# dmpcb2.net
KiCad netlist of a schematic drawn in EAGLE
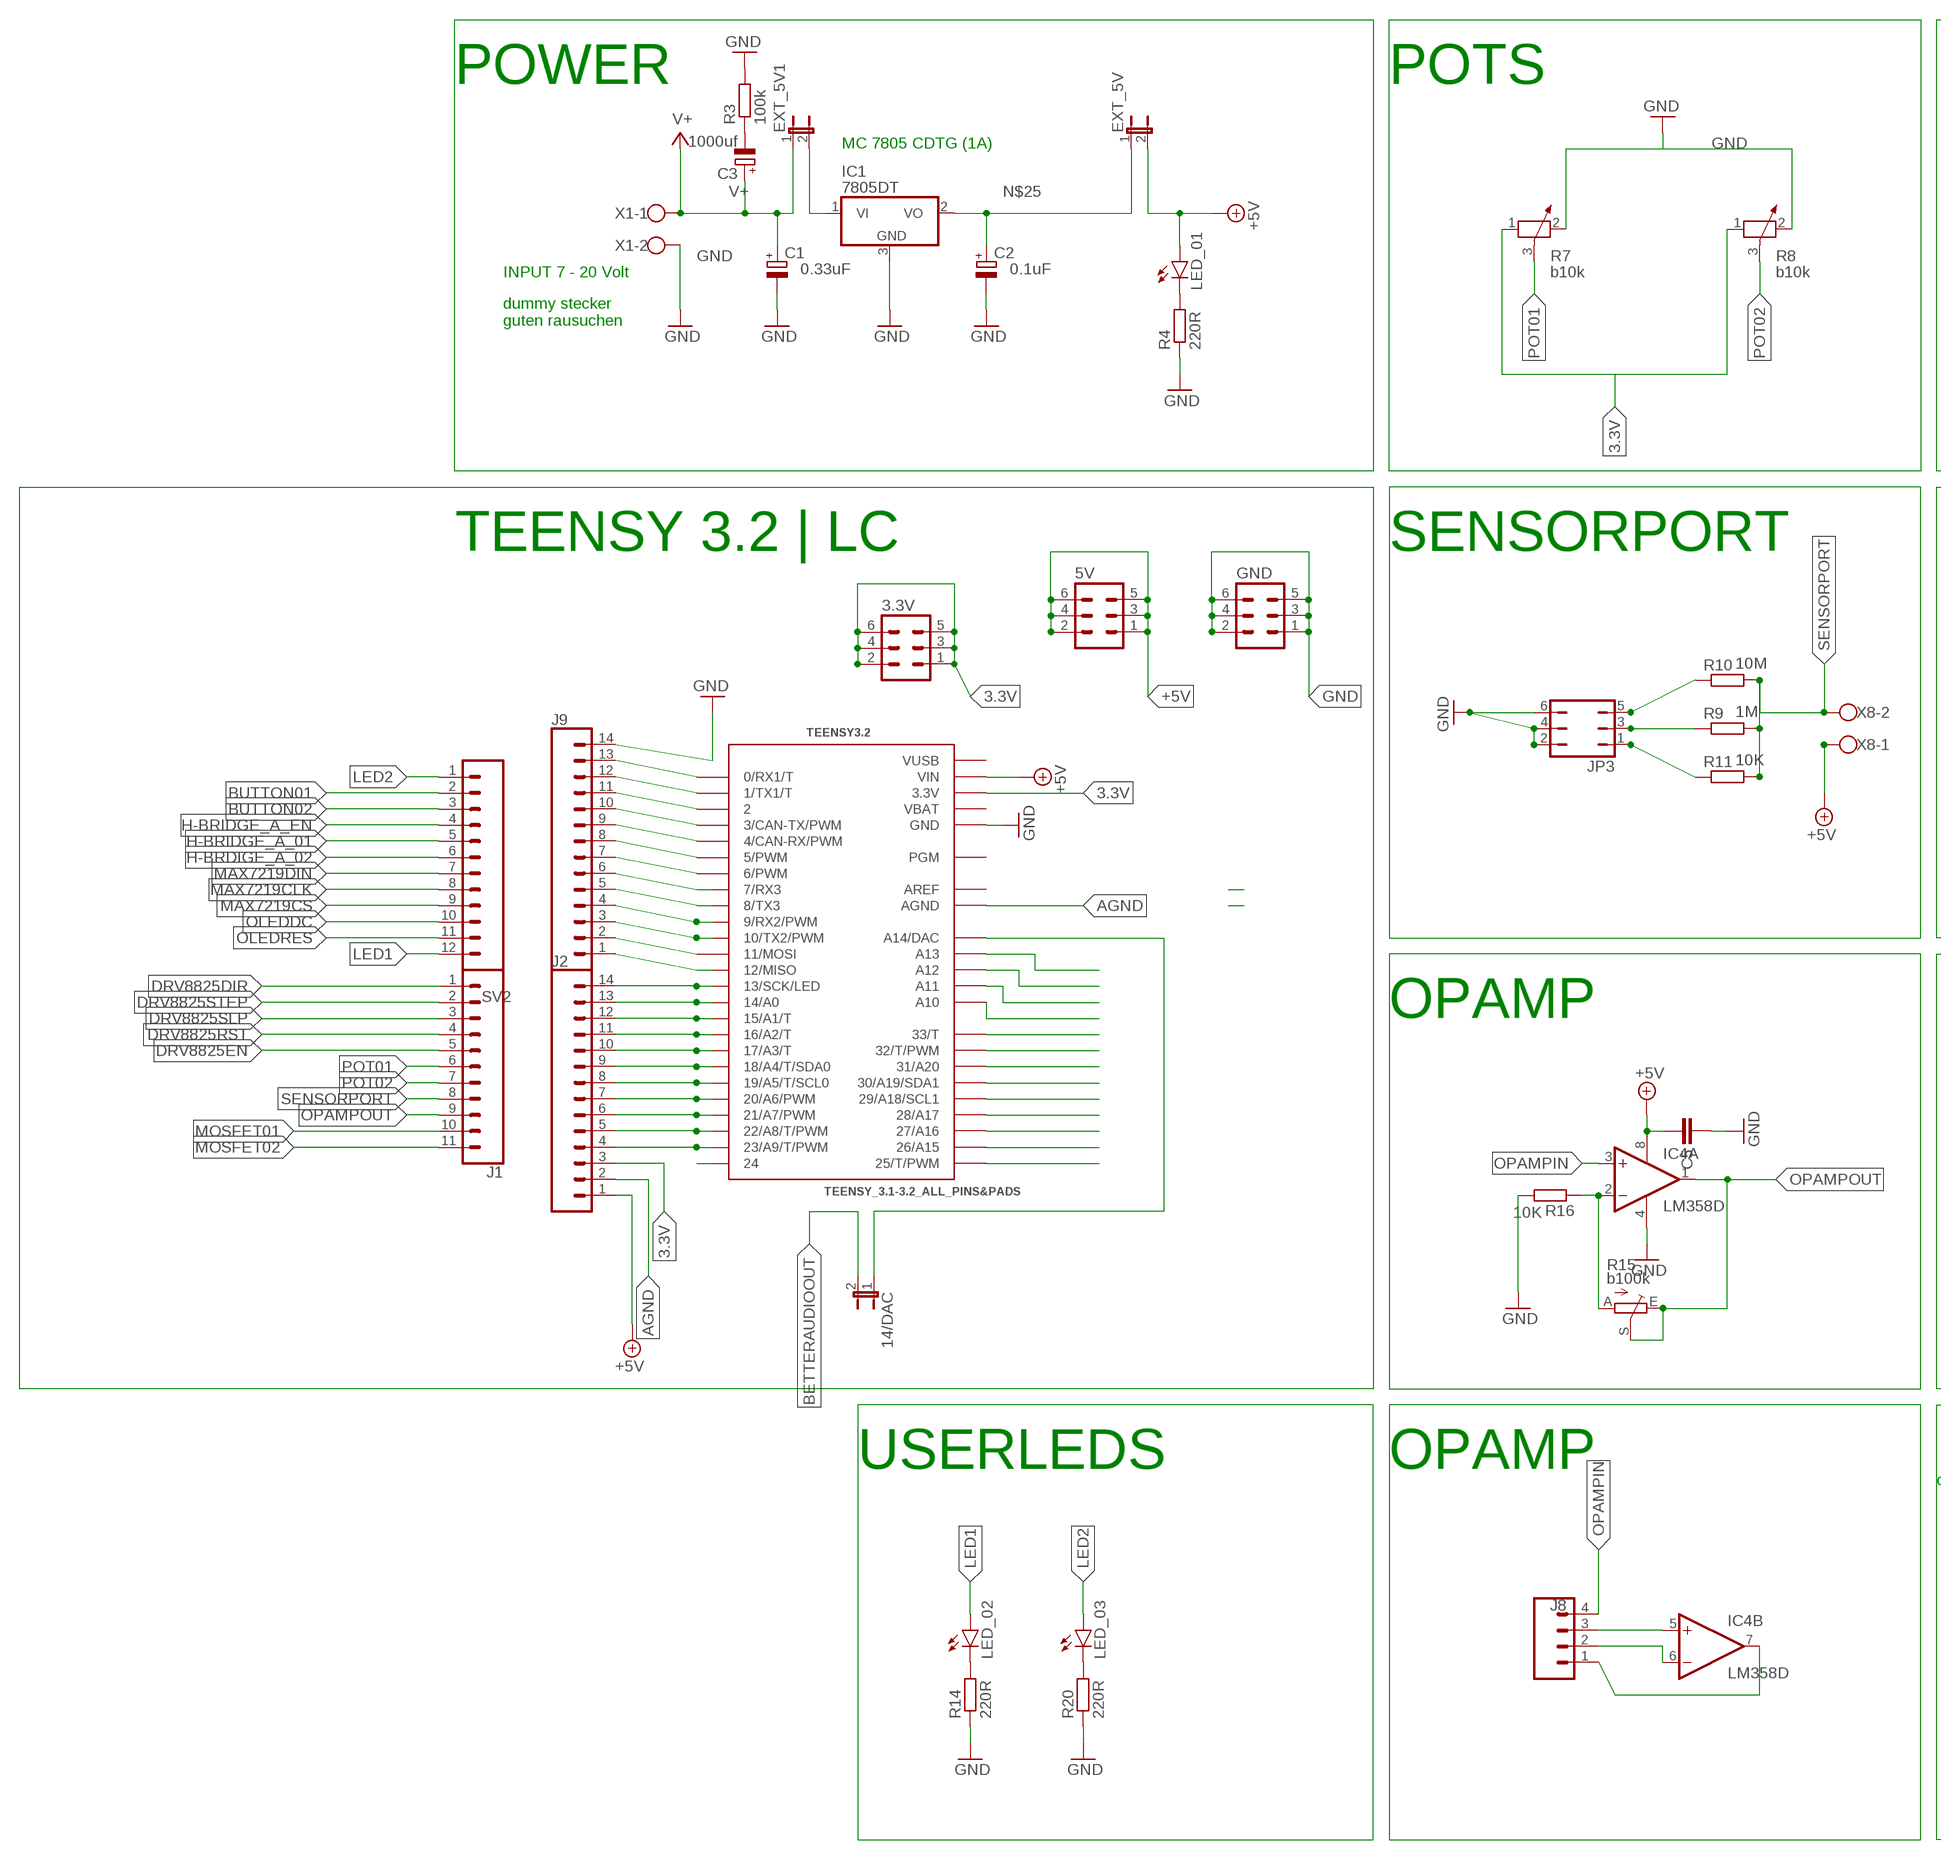
[diagram p0: schematic, sheet 1, part 1 of 2]
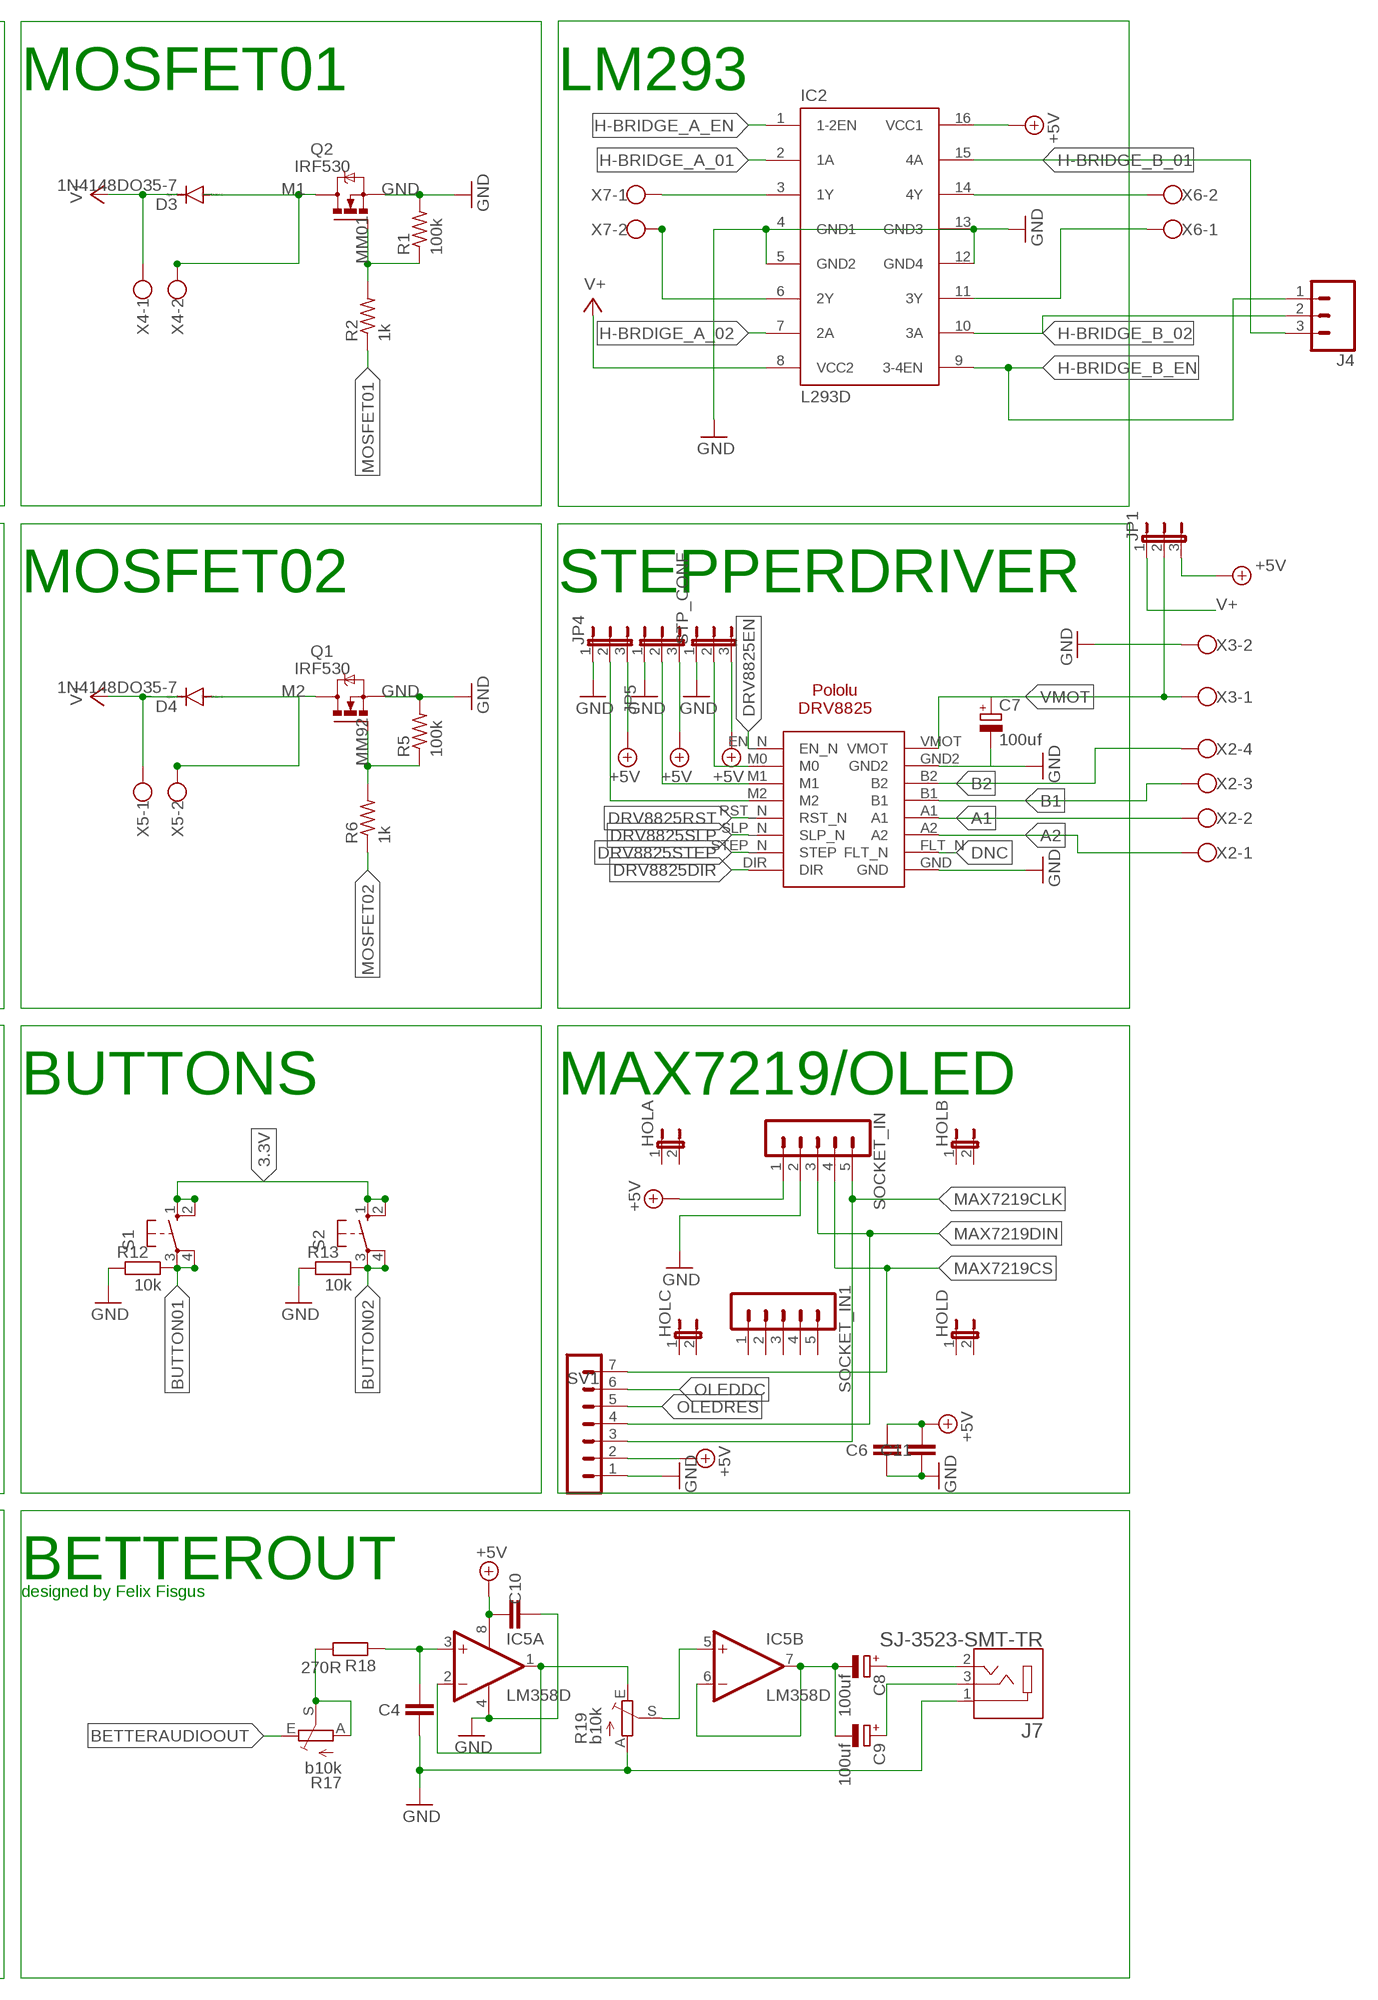
[diagram p1: schematic, sheet 1, part 2 of 2]

(export (version "E")
  (design (tool "Eeschema 10.0.6"))
  (components
    (comp (ref "3.3V")
      (value "MA03-2")
      (footprint "eagle-import:MA03-2")
      (libsource (lib "eagle-import") (part "MA03-2"))
    )
    (comp (ref "5V")
      (value "MA03-2")
      (footprint "eagle-import:MA03-2")
      (libsource (lib "eagle-import") (part "MA03-2"))
    )
    (comp (ref "14/DAC")
      (value "JP1E")
      (footprint "eagle-import:JP1")
      (libsource (lib "eagle-import") (part "JP1E"))
    )
    (comp (ref "C1")
      (value "0.33uF")
      (footprint "eagle-import:SANYO-OSCON_A'")
      (libsource (lib "eagle-import") (part "CPOL-EUSANYO_A'"))
    )
    (comp (ref "C2")
      (value "0.1uF")
      (footprint "eagle-import:SANYO-OSCON_A'")
      (libsource (lib "eagle-import") (part "CPOL-EUSANYO_A'"))
    )
    (comp (ref "C3")
      (value "1000uf")
      (footprint "eagle-import:E3,5-8")
      (libsource (lib "eagle-import") (part "CPOL-EUE3.5-8"))
    )
    (comp (ref "C4")
      (value "100nf")
      (footprint "eagle-import:C0805")
      (libsource (lib "eagle-import") (part "C-EUC0805"))
    )
    (comp (ref "C5")
      (value "100nf")
      (footprint "eagle-import:C0805")
      (libsource (lib "eagle-import") (part "C-EUC0805"))
    )
    (comp (ref "C6")
      (value "100nf")
      (footprint "eagle-import:C0805")
      (libsource (lib "eagle-import") (part "C-EUC0805"))
    )
    (comp (ref "C7")
      (value "100uf")
      (footprint "eagle-import:E5-5")
      (libsource (lib "eagle-import") (part "CPOL-EUE5-5"))
    )
    (comp (ref "C8")
      (value "100uf")
      (footprint "eagle-import:E5-5")
      (libsource (lib "eagle-import") (part "CPOL-EUE5-5"))
    )
    (comp (ref "C9")
      (value "100uf")
      (footprint "eagle-import:E5-5")
      (libsource (lib "eagle-import") (part "CPOL-EUE5-5"))
    )
    (comp (ref "C10")
      (value "100nf")
      (footprint "eagle-import:C0805")
      (libsource (lib "eagle-import") (part "C-EUC0805"))
    )
    (comp (ref "C11")
      (value "10uf")
      (footprint "eagle-import:C0805")
      (libsource (lib "eagle-import") (part "C-EUC0805"))
    )
    (comp (ref "D3")
      (value "1N4148DO35-7")
      (footprint "eagle-import:DO35-7")
      (libsource (lib "eagle-import") (part "1N4148DO35-7"))
    )
    (comp (ref "D4")
      (value "1N4148DO35-7")
      (footprint "eagle-import:DO35-7")
      (libsource (lib "eagle-import") (part "1N4148DO35-7"))
    )
    (comp (ref "DRV8825")
      (value "POLOLU-DRV8825")
      (footprint "eagle-import:POLOLU-DRV8825")
      (libsource (lib "eagle-import") (part "POLOLU-DRV8825"))
    )
    (comp (ref "EXT_5V")
      (value "JP1E")
      (footprint "eagle-import:JP1")
      (libsource (lib "eagle-import") (part "JP1E"))
    )
    (comp (ref "EXT_5V1")
      (value "JP1E")
      (footprint "eagle-import:JP1")
      (libsource (lib "eagle-import") (part "JP1E"))
    )
    (comp (ref "GND")
      (value "MA03-2")
      (footprint "eagle-import:MA03-2")
      (libsource (lib "eagle-import") (part "MA03-2"))
    )
    (comp (ref "HOLA")
      (value "JP1E")
      (footprint "eagle-import:JP1")
      (libsource (lib "eagle-import") (part "JP1E"))
    )
    (comp (ref "HOLB")
      (value "JP1E")
      (footprint "eagle-import:JP1")
      (libsource (lib "eagle-import") (part "JP1E"))
    )
    (comp (ref "HOLC")
      (value "JP1E")
      (footprint "eagle-import:JP1")
      (libsource (lib "eagle-import") (part "JP1E"))
    )
    (comp (ref "HOLD")
      (value "JP1E")
      (footprint "eagle-import:JP1")
      (libsource (lib "eagle-import") (part "JP1E"))
    )
    (comp (ref "IC1")
      (value "7805DT")
      (footprint "eagle-import:TO252")
      (libsource (lib "eagle-import") (part "78DT05"))
    )
    (comp (ref "IC2")
      (value "L293D")
      (footprint "eagle-import:DIL16")
      (libsource (lib "eagle-import") (part "L293D"))
    )
    (comp (ref "IC4")
      (value "LM358D")
      (footprint "eagle-import:SO08")
      (libsource (lib "eagle-import") (part "LM358D"))
    )
    (comp (ref "IC5")
      (value "LM358D")
      (footprint "eagle-import:SO08")
      (libsource (lib "eagle-import") (part "LM358D"))
    )
    (comp (ref "J1")
      (value "CONN_11")
      (footprint "eagle-import:1X11")
      (libsource (lib "eagle-import") (part "CONN_11"))
    )
    (comp (ref "J2")
      (value "CONN_14")
      (footprint "eagle-import:1X14")
      (libsource (lib "eagle-import") (part "CONN_14"))
    )
    (comp (ref "J4")
      (value "CONN_03LOCK_LONGPADS")
      (footprint "eagle-import:1X03_LOCK_LONGPADS")
      (libsource (lib "eagle-import") (part "CONN_03LOCK_LONGPADS"))
    )
    (comp (ref "J7")
      (value "SJ-3523-SMT-TR")
      (footprint "eagle-import:CUI_SJ-3523-SMT-TR")
      (fields (field (name "MF") "CUI Inc"))
      (libsource (lib "eagle-import") (part "SJ-3523-SMT-TR"))
    )
    (comp (ref "J8")
      (value "CONN_04")
      (footprint "eagle-import:1X04")
      (libsource (lib "eagle-import") (part "CONN_04"))
    )
    (comp (ref "J9")
      (value "CONN_14")
      (footprint "eagle-import:1X14")
      (libsource (lib "eagle-import") (part "CONN_14"))
    )
    (comp (ref "JP1")
      (value "JP2E")
      (footprint "eagle-import:JP2")
      (libsource (lib "eagle-import") (part "JP2E"))
    )
    (comp (ref "JP3")
      (value "JP3Q")
      (footprint "eagle-import:JP3Q")
      (libsource (lib "eagle-import") (part "JP3Q"))
    )
    (comp (ref "JP4")
      (value "JP2E")
      (footprint "eagle-import:JP2")
      (libsource (lib "eagle-import") (part "JP2E"))
    )
    (comp (ref "JP5")
      (value "JP2E")
      (footprint "eagle-import:JP2")
      (libsource (lib "eagle-import") (part "JP2E"))
    )
    (comp (ref "LED_01")
      (value "LEDSML0805")
      (footprint "eagle-import:SML0805")
      (libsource (lib "eagle-import") (part "LEDSML0805"))
    )
    (comp (ref "LED_02")
      (value "LEDSML0805")
      (footprint "eagle-import:SML0805")
      (libsource (lib "eagle-import") (part "LEDSML0805"))
    )
    (comp (ref "LED_03")
      (value "LEDSML0805")
      (footprint "eagle-import:SML0805")
      (libsource (lib "eagle-import") (part "LEDSML0805"))
    )
    (comp (ref "Q1")
      (value "IRF530")
      (footprint "eagle-import:TO220BV")
      (libsource (lib "eagle-import") (part "IRF530"))
    )
    (comp (ref "Q2")
      (value "IRF530")
      (footprint "eagle-import:TO220BV")
      (libsource (lib "eagle-import") (part "IRF530"))
    )
    (comp (ref "R1")
      (value "100k")
      (footprint "eagle-import:R0805")
      (libsource (lib "eagle-import") (part "R-US_R0805"))
    )
    (comp (ref "R2")
      (value "1k")
      (footprint "eagle-import:R0805")
      (libsource (lib "eagle-import") (part "R-US_R0805"))
    )
    (comp (ref "R3")
      (value "100k")
      (footprint "eagle-import:R0805")
      (libsource (lib "eagle-import") (part "R-EU_R0805"))
    )
    (comp (ref "R4")
      (value "220R")
      (footprint "eagle-import:R0805")
      (libsource (lib "eagle-import") (part "R-EU_R0805"))
    )
    (comp (ref "R5")
      (value "100k")
      (footprint "eagle-import:R0805")
      (libsource (lib "eagle-import") (part "R-US_R0805"))
    )
    (comp (ref "R6")
      (value "1k")
      (footprint "eagle-import:R0805")
      (libsource (lib "eagle-import") (part "R-US_R0805"))
    )
    (comp (ref "R7")
      (value "b10k")
      (footprint "eagle-import:PT-10")
      (libsource (lib "eagle-import") (part "POTENTIOMETER_PT-10"))
    )
    (comp (ref "R8")
      (value "b10k")
      (footprint "eagle-import:PT-10")
      (libsource (lib "eagle-import") (part "POTENTIOMETER_PT-10"))
    )
    (comp (ref "R9")
      (value "1M")
      (footprint "eagle-import:M0805")
      (libsource (lib "eagle-import") (part "R-EU_M0805"))
    )
    (comp (ref "R10")
      (value "10M")
      (footprint "eagle-import:M0805")
      (libsource (lib "eagle-import") (part "R-EU_M0805"))
    )
    (comp (ref "R11")
      (value "10K")
      (footprint "eagle-import:M0805")
      (libsource (lib "eagle-import") (part "R-EU_M0805"))
    )
    (comp (ref "R12")
      (value "10k")
      (footprint "eagle-import:M0805")
      (libsource (lib "eagle-import") (part "R-EU_M0805"))
    )
    (comp (ref "R13")
      (value "10k")
      (footprint "eagle-import:M0805")
      (libsource (lib "eagle-import") (part "R-EU_M0805"))
    )
    (comp (ref "R14")
      (value "220R")
      (footprint "eagle-import:R0805")
      (libsource (lib "eagle-import") (part "R-EU_R0805"))
    )
    (comp (ref "R15")
      (value "b100k")
      (footprint "eagle-import:RJ9W")
      (libsource (lib "eagle-import") (part "TRIM_EU-RJ9W"))
    )
    (comp (ref "R16")
      (value "10K")
      (footprint "eagle-import:M0805")
      (libsource (lib "eagle-import") (part "R-EU_M0805"))
    )
    (comp (ref "R17")
      (value "b10k")
      (footprint "eagle-import:RJ9W")
      (libsource (lib "eagle-import") (part "TRIM_EU-RJ9W"))
    )
    (comp (ref "R18")
      (value "270R")
      (footprint "eagle-import:M0805")
      (libsource (lib "eagle-import") (part "R-EU_M0805"))
    )
    (comp (ref "R19")
      (value "b10k")
      (footprint "eagle-import:RJ9W")
      (libsource (lib "eagle-import") (part "TRIM_EU-RJ9W"))
    )
    (comp (ref "R20")
      (value "220R")
      (footprint "eagle-import:R0805")
      (libsource (lib "eagle-import") (part "R-EU_R0805"))
    )
    (comp (ref "S1")
      (value "10-XX")
      (footprint "eagle-import:B3F-10XX")
      (fields (field (name "MPN") "B3F-1000"))
      (libsource (lib "eagle-import") (part "10-XX"))
    )
    (comp (ref "S2")
      (value "10-XX")
      (footprint "eagle-import:B3F-10XX")
      (fields (field (name "MPN") "B3F-1000"))
      (libsource (lib "eagle-import") (part "10-XX"))
    )
    (comp (ref "SOCKET_IN")
      (value "MA05-1")
      (footprint "eagle-import:MA05-1")
      (libsource (lib "eagle-import") (part "MA05-1"))
    )
    (comp (ref "SOCKET_IN1")
      (value "MA05-1")
      (footprint "eagle-import:MA05-1")
      (libsource (lib "eagle-import") (part "MA05-1"))
    )
    (comp (ref "STP_CONF")
      (value "JP2E")
      (footprint "eagle-import:JP2")
      (libsource (lib "eagle-import") (part "JP2E"))
    )
    (comp (ref "SV1")
      (value "MA07-1")
      (footprint "eagle-import:MA07-1")
      (libsource (lib "eagle-import") (part "MA07-1"))
    )
    (comp (ref "SV2")
      (value "CONN_12")
      (footprint "eagle-import:1X12")
      (libsource (lib "eagle-import") (part "CONN_12"))
    )
    (comp (ref "TEENSY3.2")
      (value "TEENSY_3.1-3.2_ALL_PINS&PADS")
      (footprint "eagle-import:TEENSY_3.0-3.2_ALL_PINS_&_PADS")
      (libsource (lib "eagle-import") (part "TEENSY_3.1-3.2_ALL_PINS&PADS"))
    )
    (comp (ref "X1")
      (value "W237-102")
      (footprint "eagle-import:W237-102")
      (fields (field (name "MPN") "237-102"))
      (libsource (lib "eagle-import") (part "W237-102"))
    )
    (comp (ref "X2")
      (value "W237-4")
      (footprint "eagle-import:W237-4")
      (libsource (lib "eagle-import") (part "W237-4"))
    )
    (comp (ref "X3")
      (value "W237-102")
      (footprint "eagle-import:W237-102")
      (fields (field (name "MPN") "237-102"))
      (libsource (lib "eagle-import") (part "W237-102"))
    )
    (comp (ref "X4")
      (value "W237-102")
      (footprint "eagle-import:W237-102")
      (fields (field (name "MPN") "237-102"))
      (libsource (lib "eagle-import") (part "W237-102"))
    )
    (comp (ref "X5")
      (value "W237-102")
      (footprint "eagle-import:W237-102")
      (fields (field (name "MPN") "237-102"))
      (libsource (lib "eagle-import") (part "W237-102"))
    )
    (comp (ref "X6")
      (value "W237-102")
      (footprint "eagle-import:W237-102")
      (fields (field (name "MPN") "237-102"))
      (libsource (lib "eagle-import") (part "W237-102"))
    )
    (comp (ref "X7")
      (value "W237-102")
      (footprint "eagle-import:W237-102")
      (fields (field (name "MPN") "237-102"))
      (libsource (lib "eagle-import") (part "W237-102"))
    )
    (comp (ref "X8")
      (value "W237-102")
      (footprint "eagle-import:W237-102")
      (fields (field (name "MPN") "237-102"))
      (libsource (lib "eagle-import") (part "W237-102"))
    )
  )
  (nets
    (net (code "1") (name "+5V") (class "Default")
      (node (ref "5V") (pin "1") (pinfunction "1_1") (pintype "passive"))
      (node (ref "5V") (pin "2") (pinfunction "2_2") (pintype "passive"))
      (node (ref "5V") (pin "3") (pinfunction "3_3") (pintype "passive"))
      (node (ref "5V") (pin "4") (pinfunction "4_4") (pintype "passive"))
      (node (ref "5V") (pin "5") (pinfunction "5_5") (pintype "passive"))
      (node (ref "5V") (pin "6") (pinfunction "6_6") (pintype "passive"))
      (node (ref "C10") (pin "2") (pinfunction "2_2") (pintype "passive"))
      (node (ref "C11") (pin "1") (pinfunction "1_1") (pintype "passive"))
      (node (ref "C5") (pin "1") (pinfunction "1_1") (pintype "passive"))
      (node (ref "C6") (pin "1") (pinfunction "1_1") (pintype "passive"))
      (node (ref "EXT_5V") (pin "2") (pinfunction "2_2") (pintype "passive"))
      (node (ref "IC2") (pin "16") (pinfunction "VCC1_16") (pintype "power_in"))
      (node (ref "IC4") (pin "8") (pinfunction "V+_8") (pintype "power_in"))
      (node (ref "IC5") (pin "8") (pinfunction "V+_8") (pintype "power_in"))
      (node (ref "J2") (pin "1") (pinfunction "1_1") (pintype "passive"))
      (node (ref "JP1") (pin "3") (pinfunction "3_3") (pintype "passive"))
      (node (ref "JP4") (pin "3") (pinfunction "3_3") (pintype "passive"))
      (node (ref "JP5") (pin "3") (pinfunction "3_3") (pintype "passive"))
      (node (ref "LED_01") (pin "A") (pinfunction "A_A") (pintype "passive"))
      (node (ref "SOCKET_IN") (pin "1") (pinfunction "1_1") (pintype "passive"))
      (node (ref "STP_CONF") (pin "3") (pinfunction "3_3") (pintype "passive"))
      (node (ref "SV1") (pin "2") (pinfunction "2_2") (pintype "passive"))
      (node (ref "TEENSY3.2") (pin "VIN") (pinfunction "VIN_VIN") (pintype "power_in"))
      (node (ref "X8") (pin "1") (pinfunction "KL_1") (pintype "passive"))
    )
    (net (code "2") (name "/AREF") (class "Default")
      (node (ref "TEENSY3.2") (pin "AREF") (pinfunction "AREF_AREF") (pintype "power_in"))
    )
    (net (code "3") (name "/M1") (class "Default")
      (node (ref "D3") (pin "A") (pinfunction "A_A") (pintype "passive"))
      (node (ref "Q2") (pin "D") (pinfunction "D_D") (pintype "passive"))
      (node (ref "X4") (pin "2") (pinfunction "KL_2") (pintype "passive"))
    )
    (net (code "4") (name "/M2") (class "Default")
      (node (ref "D4") (pin "A") (pinfunction "A_A") (pintype "passive"))
      (node (ref "Q1") (pin "D") (pinfunction "D_D") (pintype "passive"))
      (node (ref "X5") (pin "2") (pinfunction "KL_2") (pintype "passive"))
    )
    (net (code "5") (name "/MM01") (class "Default")
      (node (ref "Q2") (pin "G") (pinfunction "G_G") (pintype "passive"))
      (node (ref "R1") (pin "1") (pinfunction "1_1") (pintype "passive"))
      (node (ref "R2") (pin "2") (pinfunction "2_2") (pintype "passive"))
    )
    (net (code "6") (name "/MM92") (class "Default")
      (node (ref "Q1") (pin "G") (pinfunction "G_G") (pintype "passive"))
      (node (ref "R5") (pin "1") (pinfunction "1_1") (pintype "passive"))
      (node (ref "R6") (pin "2") (pinfunction "2_2") (pintype "passive"))
    )
    (net (code "7") (name "/N$25") (class "Default")
      (node (ref "C2") (pin "+") (pinfunction "+_+") (pintype "passive"))
      (node (ref "EXT_5V") (pin "1") (pinfunction "1_1") (pintype "passive"))
      (node (ref "IC1") (pin "2") (pinfunction "VO_2") (pintype "passive"))
    )
    (net (code "8") (name "/VBAT") (class "Default")
      (node (ref "TEENSY3.2") (pin "VBAT") (pinfunction "VBAT_VBAT") (pintype "power_in"))
    )
    (net (code "9") (name "/VUSB") (class "Default")
      (node (ref "TEENSY3.2") (pin "VUSB") (pinfunction "VUSB_VUSB") (pintype "power_in"))
    )
    (net (code "10") (name "3.3V") (class "Default")
      (node (ref "3.3V") (pin "1") (pinfunction "1_1") (pintype "passive"))
      (node (ref "3.3V") (pin "2") (pinfunction "2_2") (pintype "passive"))
      (node (ref "3.3V") (pin "3") (pinfunction "3_3") (pintype "passive"))
      (node (ref "3.3V") (pin "4") (pinfunction "4_4") (pintype "passive"))
      (node (ref "3.3V") (pin "5") (pinfunction "5_5") (pintype "passive"))
      (node (ref "3.3V") (pin "6") (pinfunction "6_6") (pintype "passive"))
      (node (ref "J2") (pin "3") (pinfunction "3_3") (pintype "passive"))
      (node (ref "R7") (pin "1") (pinfunction "1_1") (pintype "passive"))
      (node (ref "R8") (pin "1") (pinfunction "1_1") (pintype "passive"))
      (node (ref "S1") (pin "1") (pinfunction "S_1") (pintype "passive"))
      (node (ref "S1") (pin "2") (pinfunction "S1_2") (pintype "passive"))
      (node (ref "S2") (pin "1") (pinfunction "S_1") (pintype "passive"))
      (node (ref "S2") (pin "2") (pinfunction "S1_2") (pintype "passive"))
      (node (ref "TEENSY3.2") (pin "3.3V") (pinfunction "3.3V_3.3V") (pintype "power_in"))
      (node (ref "TEENSY3.2") (pin "3.3V1") (pinfunction "3.3V_3.3V1") (pintype "power_in"))
      (node (ref "TEENSY3.2") (pin "3.3V2") (pinfunction "3.3V_3.3V2") (pintype "power_in"))
    )
    (net (code "11") (name "A1") (class "Default")
      (node (ref "DRV8825") (pin "A1") (pinfunction "A1_A1") (pintype "bidirectional"))
      (node (ref "X2") (pin "2") (pinfunction "KL_2") (pintype "passive"))
    )
    (net (code "12") (name "A2") (class "Default")
      (node (ref "DRV8825") (pin "A2") (pinfunction "A2_A2") (pintype "bidirectional"))
      (node (ref "X2") (pin "1") (pinfunction "KL_1") (pintype "passive"))
    )
    (net (code "13") (name "AGND") (class "Default")
      (node (ref "J2") (pin "2") (pinfunction "2_2") (pintype "passive"))
      (node (ref "TEENSY3.2") (pin "AGND") (pinfunction "AGND_AGND") (pintype "power_in"))
    )
    (net (code "14") (name "B1") (class "Default")
      (node (ref "DRV8825") (pin "B1") (pinfunction "B1_B1") (pintype "bidirectional"))
      (node (ref "X2") (pin "3") (pinfunction "KL_3") (pintype "passive"))
    )
    (net (code "15") (name "B2") (class "Default")
      (node (ref "DRV8825") (pin "B2") (pinfunction "B2_B2") (pintype "bidirectional"))
      (node (ref "X2") (pin "4") (pinfunction "KL_4") (pintype "passive"))
    )
    (net (code "16") (name "BETTERAUDIOOUT") (class "Default")
      (node (ref "14/DAC") (pin "2") (pinfunction "2_2") (pintype "passive"))
      (node (ref "R17") (pin "E") (pinfunction "E_E") (pintype "passive"))
    )
    (net (code "17") (name "BUTTON01") (class "Default")
      (node (ref "R12") (pin "2") (pinfunction "2_2") (pintype "passive"))
      (node (ref "S1") (pin "3") (pinfunction "P_3") (pintype "passive"))
      (node (ref "S1") (pin "4") (pinfunction "P1_4") (pintype "passive"))
      (node (ref "SV2") (pin "2") (pinfunction "2_2") (pintype "passive"))
    )
    (net (code "18") (name "BUTTON02") (class "Default")
      (node (ref "R13") (pin "2") (pinfunction "2_2") (pintype "passive"))
      (node (ref "S2") (pin "3") (pinfunction "P_3") (pintype "passive"))
      (node (ref "S2") (pin "4") (pinfunction "P1_4") (pintype "passive"))
      (node (ref "SV2") (pin "3") (pinfunction "3_3") (pintype "passive"))
    )
    (net (code "19") (name "DNC") (class "Default")
      (node (ref "DRV8825") (pin "FLT_N") (pinfunction "FLT_N_FLT_N") (pintype "bidirectional"))
    )
    (net (code "20") (name "DRV8825DIR") (class "Default")
      (node (ref "DRV8825") (pin "DIR") (pinfunction "DIR_DIR") (pintype "bidirectional"))
      (node (ref "J1") (pin "1") (pinfunction "1_1") (pintype "passive"))
    )
    (net (code "21") (name "DRV8825EN") (class "Default")
      (node (ref "DRV8825") (pin "EN_N") (pinfunction "EN_N_EN_N") (pintype "bidirectional"))
      (node (ref "J1") (pin "5") (pinfunction "5_5") (pintype "passive"))
    )
    (net (code "22") (name "DRV8825RST") (class "Default")
      (node (ref "DRV8825") (pin "RST_N") (pinfunction "RST_N_RST_N") (pintype "bidirectional"))
      (node (ref "J1") (pin "4") (pinfunction "4_4") (pintype "passive"))
    )
    (net (code "23") (name "DRV8825SLP") (class "Default")
      (node (ref "DRV8825") (pin "SLP_N") (pinfunction "SLP_N_SLP_N") (pintype "bidirectional"))
      (node (ref "J1") (pin "3") (pinfunction "3_3") (pintype "passive"))
    )
    (net (code "24") (name "DRV8825STEP") (class "Default")
      (node (ref "DRV8825") (pin "STEP_N") (pinfunction "STEP_STEP_N") (pintype "bidirectional"))
      (node (ref "J1") (pin "2") (pinfunction "2_2") (pintype "passive"))
    )
    (net (code "25") (name "GND") (class "Default")
      (node (ref "C1") (pin "-") (pinfunction "-_-") (pintype "passive"))
      (node (ref "C10") (pin "1") (pinfunction "1_1") (pintype "passive"))
      (node (ref "C11") (pin "2") (pinfunction "2_2") (pintype "passive"))
      (node (ref "C2") (pin "-") (pinfunction "-_-") (pintype "passive"))
      (node (ref "C4") (pin "2") (pinfunction "2_2") (pintype "passive"))
      (node (ref "C5") (pin "2") (pinfunction "2_2") (pintype "passive"))
      (node (ref "C6") (pin "2") (pinfunction "2_2") (pintype "passive"))
      (node (ref "C7") (pin "-") (pinfunction "-_-") (pintype "passive"))
      (node (ref "DRV8825") (pin "GND") (pinfunction "GND_GND") (pintype "bidirectional"))
      (node (ref "DRV8825") (pin "GND2") (pinfunction "GND2_GND2") (pintype "bidirectional"))
      (node (ref "GND") (pin "1") (pinfunction "1_1") (pintype "passive"))
      (node (ref "GND") (pin "2") (pinfunction "2_2") (pintype "passive"))
      (node (ref "GND") (pin "3") (pinfunction "3_3") (pintype "passive"))
      (node (ref "GND") (pin "4") (pinfunction "4_4") (pintype "passive"))
      (node (ref "GND") (pin "5") (pinfunction "5_5") (pintype "passive"))
      (node (ref "GND") (pin "6") (pinfunction "6_6") (pintype "passive"))
      (node (ref "IC1") (pin "3") (pinfunction "GND_3") (pintype "passive"))
      (node (ref "IC2") (pin "12") (pinfunction "GND4_12") (pintype "power_in"))
      (node (ref "IC2") (pin "13") (pinfunction "GND3_13") (pintype "power_in"))
      (node (ref "IC2") (pin "4") (pinfunction "GND1_4") (pintype "power_in"))
      (node (ref "IC2") (pin "5") (pinfunction "GND2_5") (pintype "power_in"))
      (node (ref "IC4") (pin "4") (pinfunction "V-_4") (pintype "power_in"))
      (node (ref "IC5") (pin "4") (pinfunction "V-_4") (pintype "power_in"))
      (node (ref "J7") (pin "1") (pinfunction "1_1") (pintype "passive"))
      (node (ref "J9") (pin "14") (pinfunction "14_14") (pintype "passive"))
      (node (ref "JP3") (pin "2") (pinfunction "2_2") (pintype "passive"))
      (node (ref "JP3") (pin "4") (pinfunction "4_4") (pintype "passive"))
      (node (ref "JP3") (pin "6") (pinfunction "6_6") (pintype "passive"))
      (node (ref "JP4") (pin "1") (pinfunction "1_1") (pintype "passive"))
      (node (ref "JP5") (pin "1") (pinfunction "1_1") (pintype "passive"))
      (node (ref "Q1") (pin "S") (pinfunction "S_S") (pintype "passive"))
      (node (ref "Q2") (pin "S") (pinfunction "S_S") (pintype "passive"))
      (node (ref "R1") (pin "2") (pinfunction "2_2") (pintype "passive"))
      (node (ref "R12") (pin "1") (pinfunction "1_1") (pintype "passive"))
      (node (ref "R13") (pin "1") (pinfunction "1_1") (pintype "passive"))
      (node (ref "R14") (pin "1") (pinfunction "1_1") (pintype "passive"))
      (node (ref "R16") (pin "2") (pinfunction "2_2") (pintype "passive"))
      (node (ref "R19") (pin "A") (pinfunction "A_A") (pintype "passive"))
      (node (ref "R20") (pin "1") (pinfunction "1_1") (pintype "passive"))
      (node (ref "R3") (pin "2") (pinfunction "2_2") (pintype "passive"))
      (node (ref "R4") (pin "1") (pinfunction "1_1") (pintype "passive"))
      (node (ref "R5") (pin "2") (pinfunction "2_2") (pintype "passive"))
      (node (ref "R7") (pin "2") (pinfunction "2_2") (pintype "passive"))
      (node (ref "R8") (pin "2") (pinfunction "2_2") (pintype "passive"))
      (node (ref "SOCKET_IN") (pin "2") (pinfunction "2_2") (pintype "passive"))
      (node (ref "STP_CONF") (pin "1") (pinfunction "1_1") (pintype "passive"))
      (node (ref "SV1") (pin "1") (pinfunction "1_1") (pintype "passive"))
      (node (ref "TEENSY3.2") (pin "GND") (pinfunction "GND_GND") (pintype "power_in"))
      (node (ref "TEENSY3.2") (pin "GND1") (pinfunction "GND_GND1") (pintype "power_in"))
      (node (ref "TEENSY3.2") (pin "GND2") (pinfunction "GND_GND2") (pintype "power_in"))
      (node (ref "X1") (pin "2") (pinfunction "KL_2") (pintype "passive"))
      (node (ref "X3") (pin "2") (pinfunction "KL_2") (pintype "passive"))
    )
    (net (code "26") (name "H-BRDIGE_A_02") (class "Default")
      (node (ref "IC2") (pin "7") (pinfunction "2A_7") (pintype "input"))
      (node (ref "SV2") (pin "6") (pinfunction "6_6") (pintype "passive"))
    )
    (net (code "27") (name "H-BRIDGE_A_01") (class "Default")
      (node (ref "IC2") (pin "2") (pinfunction "1A_2") (pintype "input"))
      (node (ref "SV2") (pin "5") (pinfunction "5_5") (pintype "passive"))
    )
    (net (code "28") (name "H-BRIDGE_A_EN") (class "Default")
      (node (ref "IC2") (pin "1") (pinfunction "1-2EN_1") (pintype "input"))
      (node (ref "SV2") (pin "4") (pinfunction "4_4") (pintype "passive"))
    )
    (net (code "29") (name "H-BRIDGE_B_01") (class "Default")
      (node (ref "IC2") (pin "15") (pinfunction "4A_15") (pintype "input"))
      (node (ref "J4") (pin "3") (pinfunction "3_3") (pintype "passive"))
    )
    (net (code "30") (name "H-BRIDGE_B_02") (class "Default")
      (node (ref "IC2") (pin "10") (pinfunction "3A_10") (pintype "input"))
      (node (ref "J4") (pin "2") (pinfunction "2_2") (pintype "passive"))
    )
    (net (code "31") (name "H-BRIDGE_B_EN") (class "Default")
      (node (ref "IC2") (pin "9") (pinfunction "3-4EN_9") (pintype "input"))
      (node (ref "J4") (pin "1") (pinfunction "1_1") (pintype "passive"))
    )
    (net (code "32") (name "LED1") (class "Default")
      (node (ref "LED_02") (pin "A") (pinfunction "A_A") (pintype "passive"))
      (node (ref "SV2") (pin "12") (pinfunction "12_12") (pintype "passive"))
    )
    (net (code "33") (name "LED2") (class "Default")
      (node (ref "LED_03") (pin "A") (pinfunction "A_A") (pintype "passive"))
      (node (ref "SV2") (pin "1") (pinfunction "1_1") (pintype "passive"))
    )
    (net (code "34") (name "MAX7219CLK") (class "Default")
      (node (ref "SOCKET_IN") (pin "5") (pinfunction "5_5") (pintype "passive"))
      (node (ref "SV1") (pin "3") (pinfunction "3_3") (pintype "passive"))
      (node (ref "SV2") (pin "8") (pinfunction "8_8") (pintype "passive"))
    )
    (net (code "35") (name "MAX7219CS") (class "Default")
      (node (ref "SOCKET_IN") (pin "4") (pinfunction "4_4") (pintype "passive"))
      (node (ref "SV1") (pin "7") (pinfunction "7_7") (pintype "passive"))
      (node (ref "SV2") (pin "9") (pinfunction "9_9") (pintype "passive"))
    )
    (net (code "36") (name "MAX7219DIN") (class "Default")
      (node (ref "SOCKET_IN") (pin "3") (pinfunction "3_3") (pintype "passive"))
      (node (ref "SV1") (pin "4") (pinfunction "4_4") (pintype "passive"))
      (node (ref "SV2") (pin "7") (pinfunction "7_7") (pintype "passive"))
    )
    (net (code "37") (name "MOSFET01") (class "Default")
      (node (ref "J1") (pin "10") (pinfunction "10_10") (pintype "passive"))
      (node (ref "R2") (pin "1") (pinfunction "1_1") (pintype "passive"))
    )
    (net (code "38") (name "MOSFET02") (class "Default")
      (node (ref "J1") (pin "11") (pinfunction "11_11") (pintype "passive"))
      (node (ref "R6") (pin "1") (pinfunction "1_1") (pintype "passive"))
    )
    (net (code "39") (name "Net-(C3-Pad-)") (class "Default")
      (node (ref "C3") (pin "-") (pinfunction "-_-") (pintype "passive"))
      (node (ref "R3") (pin "1") (pinfunction "1_1") (pintype "passive"))
    )
    (net (code "40") (name "Net-(C8-Pad+)") (class "Default")
      (node (ref "C8") (pin "+") (pinfunction "+_+") (pintype "passive"))
      (node (ref "J7") (pin "2") (pinfunction "2_2") (pintype "passive"))
    )
    (net (code "41") (name "Net-(C9-Pad+)") (class "Default")
      (node (ref "C9") (pin "+") (pinfunction "+_+") (pintype "passive"))
      (node (ref "J7") (pin "3") (pinfunction "3_3") (pintype "passive"))
    )
    (net (code "42") (name "Net-(DRV8825-PadM0)") (class "Default")
      (node (ref "DRV8825") (pin "M0") (pinfunction "M0_M0") (pintype "bidirectional"))
      (node (ref "STP_CONF") (pin "2") (pinfunction "2_2") (pintype "passive"))
    )
    (net (code "43") (name "Net-(DRV8825-PadM1)") (class "Default")
      (node (ref "DRV8825") (pin "M1") (pinfunction "M1_M1") (pintype "bidirectional"))
      (node (ref "JP5") (pin "2") (pinfunction "2_2") (pintype "passive"))
    )
    (net (code "44") (name "Net-(DRV8825-PadM2)") (class "Default")
      (node (ref "DRV8825") (pin "M2") (pinfunction "M2_M2") (pintype "bidirectional"))
      (node (ref "JP4") (pin "2") (pinfunction "2_2") (pintype "passive"))
    )
    (net (code "45") (name "Net-(IC1-VI)") (class "Default")
      (node (ref "EXT_5V1") (pin "2") (pinfunction "2_2") (pintype "passive"))
      (node (ref "IC1") (pin "1") (pinfunction "VI_1") (pintype "input"))
    )
    (net (code "46") (name "Net-(IC2-1Y)") (class "Default")
      (node (ref "IC2") (pin "3") (pinfunction "1Y_3") (pintype "output"))
      (node (ref "X7") (pin "1") (pinfunction "KL_1") (pintype "passive"))
    )
    (net (code "47") (name "Net-(IC2-2Y)") (class "Default")
      (node (ref "IC2") (pin "6") (pinfunction "2Y_6") (pintype "output"))
      (node (ref "X7") (pin "2") (pinfunction "KL_2") (pintype "passive"))
    )
    (net (code "48") (name "Net-(IC2-3Y)") (class "Default")
      (node (ref "IC2") (pin "11") (pinfunction "3Y_11") (pintype "output"))
      (node (ref "X6") (pin "1") (pinfunction "KL_1") (pintype "passive"))
    )
    (net (code "49") (name "Net-(IC2-4Y)") (class "Default")
      (node (ref "IC2") (pin "14") (pinfunction "4Y_14") (pintype "output"))
      (node (ref "X6") (pin "2") (pinfunction "KL_2") (pintype "passive"))
    )
    (net (code "50") (name "Net-(IC4A--IN)") (class "Default")
      (node (ref "IC4") (pin "2") (pinfunction "-IN_2") (pintype "input"))
      (node (ref "R15") (pin "A") (pinfunction "A_A") (pintype "passive"))
      (node (ref "R16") (pin "1") (pinfunction "1_1") (pintype "passive"))
    )
    (net (code "51") (name "Net-(IC4B-+IN)") (class "Default")
      (node (ref "IC4") (pin "5") (pinfunction "+IN_5") (pintype "input"))
      (node (ref "J8") (pin "3") (pinfunction "3_3") (pintype "passive"))
    )
    (net (code "52") (name "Net-(IC4B--IN)") (class "Default")
      (node (ref "IC4") (pin "6") (pinfunction "-IN_6") (pintype "input"))
      (node (ref "J8") (pin "2") (pinfunction "2_2") (pintype "passive"))
    )
    (net (code "53") (name "Net-(IC4B-OUT)") (class "Default")
      (node (ref "IC4") (pin "7") (pinfunction "OUT_7") (pintype "output"))
      (node (ref "J8") (pin "1") (pinfunction "1_1") (pintype "passive"))
    )
    (net (code "54") (name "Net-(IC5A-+IN)") (class "Default")
      (node (ref "C4") (pin "1") (pinfunction "1_1") (pintype "passive"))
      (node (ref "IC5") (pin "3") (pinfunction "+IN_3") (pintype "input"))
      (node (ref "R18") (pin "1") (pinfunction "1_1") (pintype "passive"))
    )
    (net (code "55") (name "Net-(IC5A--IN)") (class "Default")
      (node (ref "IC5") (pin "1") (pinfunction "OUT_1") (pintype "output"))
      (node (ref "IC5") (pin "2") (pinfunction "-IN_2") (pintype "input"))
      (node (ref "R19") (pin "E") (pinfunction "E_E") (pintype "passive"))
    )
    (net (code "56") (name "Net-(IC5B-+IN)") (class "Default")
      (node (ref "IC5") (pin "5") (pinfunction "+IN_5") (pintype "input"))
      (node (ref "R19") (pin "S") (pinfunction "S_S") (pintype "passive"))
    )
    (net (code "57") (name "Net-(IC5B--IN)") (class "Default")
      (node (ref "C8") (pin "-") (pinfunction "-_-") (pintype "passive"))
      (node (ref "C9") (pin "-") (pinfunction "-_-") (pintype "passive"))
      (node (ref "IC5") (pin "6") (pinfunction "-IN_6") (pintype "input"))
      (node (ref "IC5") (pin "7") (pinfunction "OUT_7") (pintype "output"))
    )
    (net (code "58") (name "Net-(J2-Pad13)") (class "Default")
      (node (ref "J2") (pin "13") (pinfunction "13_13") (pintype "passive"))
      (node (ref "TEENSY3.2") (pin "14/A0") (pinfunction "14/A0_14/A0") (pintype "bidirectional"))
    )
    (net (code "59") (name "Net-(J9-Pad11)") (class "Default")
      (node (ref "J9") (pin "11") (pinfunction "11_11") (pintype "passive"))
      (node (ref "TEENSY3.2") (pin "2") (pinfunction "2_2") (pintype "bidirectional"))
    )
    (net (code "60") (name "Net-(JP3-Pad1)") (class "Default")
      (node (ref "JP3") (pin "1") (pinfunction "1_1") (pintype "passive"))
      (node (ref "R11") (pin "1") (pinfunction "1_1") (pintype "passive"))
    )
    (net (code "61") (name "Net-(JP3-Pad3)") (class "Default")
      (node (ref "JP3") (pin "3") (pinfunction "3_3") (pintype "passive"))
      (node (ref "R9") (pin "1") (pinfunction "1_1") (pintype "passive"))
    )
    (net (code "62") (name "Net-(JP3-Pad5)") (class "Default")
      (node (ref "JP3") (pin "5") (pinfunction "5_5") (pintype "passive"))
      (node (ref "R10") (pin "1") (pinfunction "1_1") (pintype "passive"))
    )
    (net (code "63") (name "Net-(LED_01-PadC)") (class "Default")
      (node (ref "LED_01") (pin "C") (pinfunction "C_C") (pintype "passive"))
      (node (ref "R4") (pin "2") (pinfunction "2_2") (pintype "passive"))
    )
    (net (code "64") (name "Net-(LED_02-PadC)") (class "Default")
      (node (ref "LED_02") (pin "C") (pinfunction "C_C") (pintype "passive"))
      (node (ref "R14") (pin "2") (pinfunction "2_2") (pintype "passive"))
    )
    (net (code "65") (name "Net-(LED_03-PadC)") (class "Default")
      (node (ref "LED_03") (pin "C") (pinfunction "C_C") (pintype "passive"))
      (node (ref "R20") (pin "2") (pinfunction "2_2") (pintype "passive"))
    )
    (net (code "66") (name "Net-(R17-PadA)") (class "Default")
      (node (ref "R17") (pin "A") (pinfunction "A_A") (pintype "passive"))
      (node (ref "R17") (pin "S") (pinfunction "S_S") (pintype "passive"))
      (node (ref "R18") (pin "2") (pinfunction "2_2") (pintype "passive"))
    )
    (net (code "67") (name "Net-(TEENSY3.2-0{slash}RX1{slash}T)") (class "Default")
      (node (ref "J9") (pin "13") (pinfunction "13_13") (pintype "passive"))
      (node (ref "TEENSY3.2") (pin "0") (pinfunction "0/RX1/T_0") (pintype "bidirectional"))
    )
    (net (code "68") (name "Net-(TEENSY3.2-1{slash}TX1{slash}T)") (class "Default")
      (node (ref "J9") (pin "12") (pinfunction "12_12") (pintype "passive"))
      (node (ref "TEENSY3.2") (pin "1") (pinfunction "1/TX1/T_1") (pintype "bidirectional"))
    )
    (net (code "69") (name "Net-(TEENSY3.2-3{slash}CAN-TX{slash}PWM)") (class "Default")
      (node (ref "J9") (pin "10") (pinfunction "10_10") (pintype "passive"))
      (node (ref "TEENSY3.2") (pin "3") (pinfunction "3/CAN-TX/PWM_3") (pintype "bidirectional"))
    )
    (net (code "70") (name "Net-(TEENSY3.2-4{slash}CAN-RX{slash}PWM)") (class "Default")
      (node (ref "J9") (pin "9") (pinfunction "9_9") (pintype "passive"))
      (node (ref "TEENSY3.2") (pin "4") (pinfunction "4/CAN-RX/PWM_4") (pintype "bidirectional"))
    )
    (net (code "71") (name "Net-(TEENSY3.2-5{slash}PWM)") (class "Default")
      (node (ref "J9") (pin "8") (pinfunction "8_8") (pintype "passive"))
      (node (ref "TEENSY3.2") (pin "5") (pinfunction "5/PWM_5") (pintype "bidirectional"))
    )
    (net (code "72") (name "Net-(TEENSY3.2-6{slash}PWM)") (class "Default")
      (node (ref "J9") (pin "7") (pinfunction "7_7") (pintype "passive"))
      (node (ref "TEENSY3.2") (pin "6") (pinfunction "6/PWM_6") (pintype "bidirectional"))
    )
    (net (code "73") (name "Net-(TEENSY3.2-7{slash}RX3)") (class "Default")
      (node (ref "J9") (pin "6") (pinfunction "6_6") (pintype "passive"))
      (node (ref "TEENSY3.2") (pin "7") (pinfunction "7/RX3_7") (pintype "bidirectional"))
    )
    (net (code "74") (name "Net-(TEENSY3.2-8{slash}TX3)") (class "Default")
      (node (ref "J9") (pin "5") (pinfunction "5_5") (pintype "passive"))
      (node (ref "TEENSY3.2") (pin "8") (pinfunction "8/TX3_8") (pintype "bidirectional"))
    )
    (net (code "75") (name "Net-(TEENSY3.2-9{slash}RX2{slash}PWM)") (class "Default")
      (node (ref "J9") (pin "4") (pinfunction "4_4") (pintype "passive"))
      (node (ref "TEENSY3.2") (pin "9") (pinfunction "9/RX2/PWM_9") (pintype "bidirectional"))
    )
    (net (code "76") (name "Net-(TEENSY3.2-10{slash}TX2{slash}PWM)") (class "Default")
      (node (ref "J9") (pin "3") (pinfunction "3_3") (pintype "passive"))
      (node (ref "TEENSY3.2") (pin "10") (pinfunction "10/TX2/PWM_10") (pintype "bidirectional"))
    )
    (net (code "77") (name "Net-(TEENSY3.2-11{slash}MOSI)") (class "Default")
      (node (ref "J9") (pin "2") (pinfunction "2_2") (pintype "passive"))
      (node (ref "TEENSY3.2") (pin "11") (pinfunction "11/MOSI_11") (pintype "bidirectional"))
    )
    (net (code "78") (name "Net-(TEENSY3.2-12{slash}MISO)") (class "Default")
      (node (ref "J9") (pin "1") (pinfunction "1_1") (pintype "passive"))
      (node (ref "TEENSY3.2") (pin "12") (pinfunction "12/MISO_12") (pintype "bidirectional"))
    )
    (net (code "79") (name "Net-(TEENSY3.2-13{slash}SCK{slash}LED)") (class "Default")
      (node (ref "J2") (pin "14") (pinfunction "14_14") (pintype "passive"))
      (node (ref "TEENSY3.2") (pin "13") (pinfunction "13/SCK/LED_13") (pintype "bidirectional"))
    )
    (net (code "80") (name "Net-(TEENSY3.2-15{slash}A1{slash}T)") (class "Default")
      (node (ref "J2") (pin "12") (pinfunction "12_12") (pintype "passive"))
      (node (ref "TEENSY3.2") (pin "15/A1") (pinfunction "15/A1/T_15/A1") (pintype "bidirectional"))
    )
    (net (code "81") (name "Net-(TEENSY3.2-16{slash}A2{slash}T)") (class "Default")
      (node (ref "J2") (pin "11") (pinfunction "11_11") (pintype "passive"))
      (node (ref "TEENSY3.2") (pin "16/A2") (pinfunction "16/A2/T_16/A2") (pintype "bidirectional"))
    )
    (net (code "82") (name "Net-(TEENSY3.2-17{slash}A3{slash}T)") (class "Default")
      (node (ref "J2") (pin "10") (pinfunction "10_10") (pintype "passive"))
      (node (ref "TEENSY3.2") (pin "17/A3") (pinfunction "17/A3/T_17/A3") (pintype "bidirectional"))
    )
    (net (code "83") (name "Net-(TEENSY3.2-18{slash}A4{slash}T{slash}SDA0)") (class "Default")
      (node (ref "J2") (pin "9") (pinfunction "9_9") (pintype "passive"))
      (node (ref "TEENSY3.2") (pin "18/A4") (pinfunction "18/A4/T/SDA0_18/A4") (pintype "bidirectional"))
    )
    (net (code "84") (name "Net-(TEENSY3.2-19{slash}A5{slash}T{slash}SCL0)") (class "Default")
      (node (ref "J2") (pin "8") (pinfunction "8_8") (pintype "passive"))
      (node (ref "TEENSY3.2") (pin "19/A5") (pinfunction "19/A5/T/SCL0_19/A5") (pintype "bidirectional"))
    )
    (net (code "85") (name "Net-(TEENSY3.2-20{slash}A6{slash}PWM)") (class "Default")
      (node (ref "J2") (pin "7") (pinfunction "7_7") (pintype "passive"))
      (node (ref "TEENSY3.2") (pin "20/A6") (pinfunction "20/A6/PWM_20/A6") (pintype "bidirectional"))
    )
    (net (code "86") (name "Net-(TEENSY3.2-21{slash}A7{slash}PWM)") (class "Default")
      (node (ref "J2") (pin "6") (pinfunction "6_6") (pintype "passive"))
      (node (ref "TEENSY3.2") (pin "21/A7") (pinfunction "21/A7/PWM_21/A7") (pintype "bidirectional"))
    )
    (net (code "87") (name "Net-(TEENSY3.2-22{slash}A8{slash}T{slash}PWM)") (class "Default")
      (node (ref "J2") (pin "5") (pinfunction "5_5") (pintype "passive"))
      (node (ref "TEENSY3.2") (pin "22/A8") (pinfunction "22/A8/T/PWM_22/A8") (pintype "bidirectional"))
    )
    (net (code "88") (name "Net-(TEENSY3.2-23{slash}A9{slash}T{slash}PWM)") (class "Default")
      (node (ref "J2") (pin "4") (pinfunction "4_4") (pintype "passive"))
      (node (ref "TEENSY3.2") (pin "23/A9") (pinfunction "23/A9/T/PWM_23/A9") (pintype "bidirectional"))
    )
    (net (code "89") (name "Net-(TEENSY3.2-A14{slash}DAC)") (class "Default")
      (node (ref "14/DAC") (pin "1") (pinfunction "1_1") (pintype "passive"))
      (node (ref "TEENSY3.2") (pin "RESET/DAC") (pinfunction "A14/DAC_RESET/DAC") (pintype "bidirectional"))
    )
    (net (code "90") (name "OLEDDC") (class "Default")
      (node (ref "SV1") (pin "6") (pinfunction "6_6") (pintype "passive"))
      (node (ref "SV2") (pin "10") (pinfunction "10_10") (pintype "passive"))
    )
    (net (code "91") (name "OLEDRES") (class "Default")
      (node (ref "SV1") (pin "5") (pinfunction "5_5") (pintype "passive"))
      (node (ref "SV2") (pin "11") (pinfunction "11_11") (pintype "passive"))
    )
    (net (code "92") (name "OPAMPIN") (class "Default")
      (node (ref "IC4") (pin "3") (pinfunction "+IN_3") (pintype "input"))
      (node (ref "J8") (pin "4") (pinfunction "4_4") (pintype "passive"))
    )
    (net (code "93") (name "OPAMPOUT") (class "Default")
      (node (ref "IC4") (pin "1") (pinfunction "OUT_1") (pintype "output"))
      (node (ref "J1") (pin "9") (pinfunction "9_9") (pintype "passive"))
      (node (ref "R15") (pin "E") (pinfunction "E_E") (pintype "passive"))
      (node (ref "R15") (pin "S") (pinfunction "S_S") (pintype "passive"))
    )
    (net (code "94") (name "POT01") (class "Default")
      (node (ref "J1") (pin "6") (pinfunction "6_6") (pintype "passive"))
      (node (ref "R7") (pin "3") (pinfunction "3_3") (pintype "passive"))
    )
    (net (code "95") (name "POT02") (class "Default")
      (node (ref "J1") (pin "7") (pinfunction "7_7") (pintype "passive"))
      (node (ref "R8") (pin "3") (pinfunction "3_3") (pintype "passive"))
    )
    (net (code "96") (name "SENSORPORT") (class "Default")
      (node (ref "J1") (pin "8") (pinfunction "8_8") (pintype "passive"))
      (node (ref "R10") (pin "2") (pinfunction "2_2") (pintype "passive"))
      (node (ref "R11") (pin "2") (pinfunction "2_2") (pintype "passive"))
      (node (ref "R9") (pin "2") (pinfunction "2_2") (pintype "passive"))
      (node (ref "X8") (pin "2") (pinfunction "KL_2") (pintype "passive"))
    )
    (net (code "97") (name "V+") (class "Default")
      (node (ref "C1") (pin "+") (pinfunction "+_+") (pintype "passive"))
      (node (ref "C3") (pin "+") (pinfunction "+_+") (pintype "passive"))
      (node (ref "D3") (pin "C") (pinfunction "C_C") (pintype "passive"))
      (node (ref "D4") (pin "C") (pinfunction "C_C") (pintype "passive"))
      (node (ref "EXT_5V1") (pin "1") (pinfunction "1_1") (pintype "passive"))
      (node (ref "IC2") (pin "8") (pinfunction "VCC2_8") (pintype "power_in"))
      (node (ref "JP1") (pin "1") (pinfunction "1_1") (pintype "passive"))
      (node (ref "X1") (pin "1") (pinfunction "KL_1") (pintype "passive"))
      (node (ref "X4") (pin "1") (pinfunction "KL_1") (pintype "passive"))
      (node (ref "X5") (pin "1") (pinfunction "KL_1") (pintype "passive"))
    )
    (net (code "98") (name "VMOT") (class "Default")
      (node (ref "C7") (pin "+") (pinfunction "+_+") (pintype "passive"))
      (node (ref "DRV8825") (pin "VMOT") (pinfunction "VMOT_VMOT") (pintype "bidirectional"))
      (node (ref "JP1") (pin "2") (pinfunction "2_2") (pintype "passive"))
      (node (ref "X3") (pin "1") (pinfunction "KL_1") (pintype "passive"))
    )
    (net (code "99") (name "unconnected-(HOLA-Pad1)") (class "Default")
      (node (ref "HOLA") (pin "1") (pinfunction "1_1") (pintype "passive"))
    )
    (net (code "100") (name "unconnected-(HOLA-Pad2)") (class "Default")
      (node (ref "HOLA") (pin "2") (pinfunction "2_2") (pintype "passive"))
    )
    (net (code "101") (name "unconnected-(HOLB-Pad1)") (class "Default")
      (node (ref "HOLB") (pin "1") (pinfunction "1_1") (pintype "passive"))
    )
    (net (code "102") (name "unconnected-(HOLB-Pad2)") (class "Default")
      (node (ref "HOLB") (pin "2") (pinfunction "2_2") (pintype "passive"))
    )
    (net (code "103") (name "unconnected-(HOLC-Pad1)") (class "Default")
      (node (ref "HOLC") (pin "1") (pinfunction "1_1") (pintype "passive"))
    )
    (net (code "104") (name "unconnected-(HOLC-Pad2)") (class "Default")
      (node (ref "HOLC") (pin "2") (pinfunction "2_2") (pintype "passive"))
    )
    (net (code "105") (name "unconnected-(HOLD-Pad1)") (class "Default")
      (node (ref "HOLD") (pin "1") (pinfunction "1_1") (pintype "passive"))
    )
    (net (code "106") (name "unconnected-(HOLD-Pad2)") (class "Default")
      (node (ref "HOLD") (pin "2") (pinfunction "2_2") (pintype "passive"))
    )
    (net (code "107") (name "unconnected-(SOCKET_IN1-Pad1)") (class "Default")
      (node (ref "SOCKET_IN1") (pin "1") (pinfunction "1_1") (pintype "passive"))
    )
    (net (code "108") (name "unconnected-(SOCKET_IN1-Pad2)") (class "Default")
      (node (ref "SOCKET_IN1") (pin "2") (pinfunction "2_2") (pintype "passive"))
    )
    (net (code "109") (name "unconnected-(SOCKET_IN1-Pad3)") (class "Default")
      (node (ref "SOCKET_IN1") (pin "3") (pinfunction "3_3") (pintype "passive"))
    )
    (net (code "110") (name "unconnected-(SOCKET_IN1-Pad4)") (class "Default")
      (node (ref "SOCKET_IN1") (pin "4") (pinfunction "4_4") (pintype "passive"))
    )
    (net (code "111") (name "unconnected-(SOCKET_IN1-Pad5)") (class "Default")
      (node (ref "SOCKET_IN1") (pin "5") (pinfunction "5_5") (pintype "passive"))
    )
    (net (code "112") (name "unconnected-(TEENSY3.2-25{slash}T{slash}PWM-Pad25)") (class "Default")
      (node (ref "TEENSY3.2") (pin "25") (pinfunction "25/T/PWM_25") (pintype "bidirectional"))
    )
    (net (code "113") (name "unconnected-(TEENSY3.2-26{slash}A15-Pad26)") (class "Default")
      (node (ref "TEENSY3.2") (pin "26") (pinfunction "26/A15_26") (pintype "bidirectional"))
    )
    (net (code "114") (name "unconnected-(TEENSY3.2-27{slash}A16-Pad27)") (class "Default")
      (node (ref "TEENSY3.2") (pin "27") (pinfunction "27/A16_27") (pintype "bidirectional"))
    )
    (net (code "115") (name "unconnected-(TEENSY3.2-28{slash}A17-Pad28)") (class "Default")
      (node (ref "TEENSY3.2") (pin "28") (pinfunction "28/A17_28") (pintype "bidirectional"))
    )
    (net (code "116") (name "unconnected-(TEENSY3.2-29{slash}A18{slash}SCL1-Pad29)") (class "Default")
      (node (ref "TEENSY3.2") (pin "29") (pinfunction "29/A18/SCL1_29") (pintype "bidirectional"))
    )
    (net (code "117") (name "unconnected-(TEENSY3.2-30{slash}A19{slash}SDA1-Pad30)") (class "Default")
      (node (ref "TEENSY3.2") (pin "30") (pinfunction "30/A19/SDA1_30") (pintype "bidirectional"))
    )
    (net (code "118") (name "unconnected-(TEENSY3.2-31{slash}A20-Pad31)") (class "Default")
      (node (ref "TEENSY3.2") (pin "31") (pinfunction "31/A20_31") (pintype "bidirectional"))
    )
    (net (code "119") (name "unconnected-(TEENSY3.2-32{slash}T{slash}PWM-Pad32)") (class "Default")
      (node (ref "TEENSY3.2") (pin "32") (pinfunction "32/T/PWM_32") (pintype "bidirectional"))
    )
    (net (code "120") (name "unconnected-(TEENSY3.2-33{slash}T-Pad33)") (class "Default")
      (node (ref "TEENSY3.2") (pin "33") (pinfunction "33/T_33") (pintype "bidirectional"))
    )
    (net (code "121") (name "unconnected-(TEENSY3.2-Pad24)") (class "Default")
      (node (ref "TEENSY3.2") (pin "24") (pinfunction "24_24") (pintype "bidirectional"))
    )
    (net (code "122") (name "unconnected-(TEENSY3.2-PadA10)") (class "Default")
      (node (ref "TEENSY3.2") (pin "A10") (pinfunction "A10_A10") (pintype "bidirectional"))
    )
    (net (code "123") (name "unconnected-(TEENSY3.2-PadA11)") (class "Default")
      (node (ref "TEENSY3.2") (pin "A11") (pinfunction "A11_A11") (pintype "bidirectional"))
    )
    (net (code "124") (name "unconnected-(TEENSY3.2-PadA12)") (class "Default")
      (node (ref "TEENSY3.2") (pin "A12") (pinfunction "A12_A12") (pintype "bidirectional"))
    )
    (net (code "125") (name "unconnected-(TEENSY3.2-PadA13)") (class "Default")
      (node (ref "TEENSY3.2") (pin "A13") (pinfunction "A13_A13") (pintype "bidirectional"))
    )
    (net (code "126") (name "unconnected-(TEENSY3.2-PadPGM)") (class "Default")
      (node (ref "TEENSY3.2") (pin "PGM") (pinfunction "PGM_PGM") (pintype "bidirectional"))
    )
  )
)
